# PowerManager.net
KiCad netlist of a schematic drawn in Altium Designer
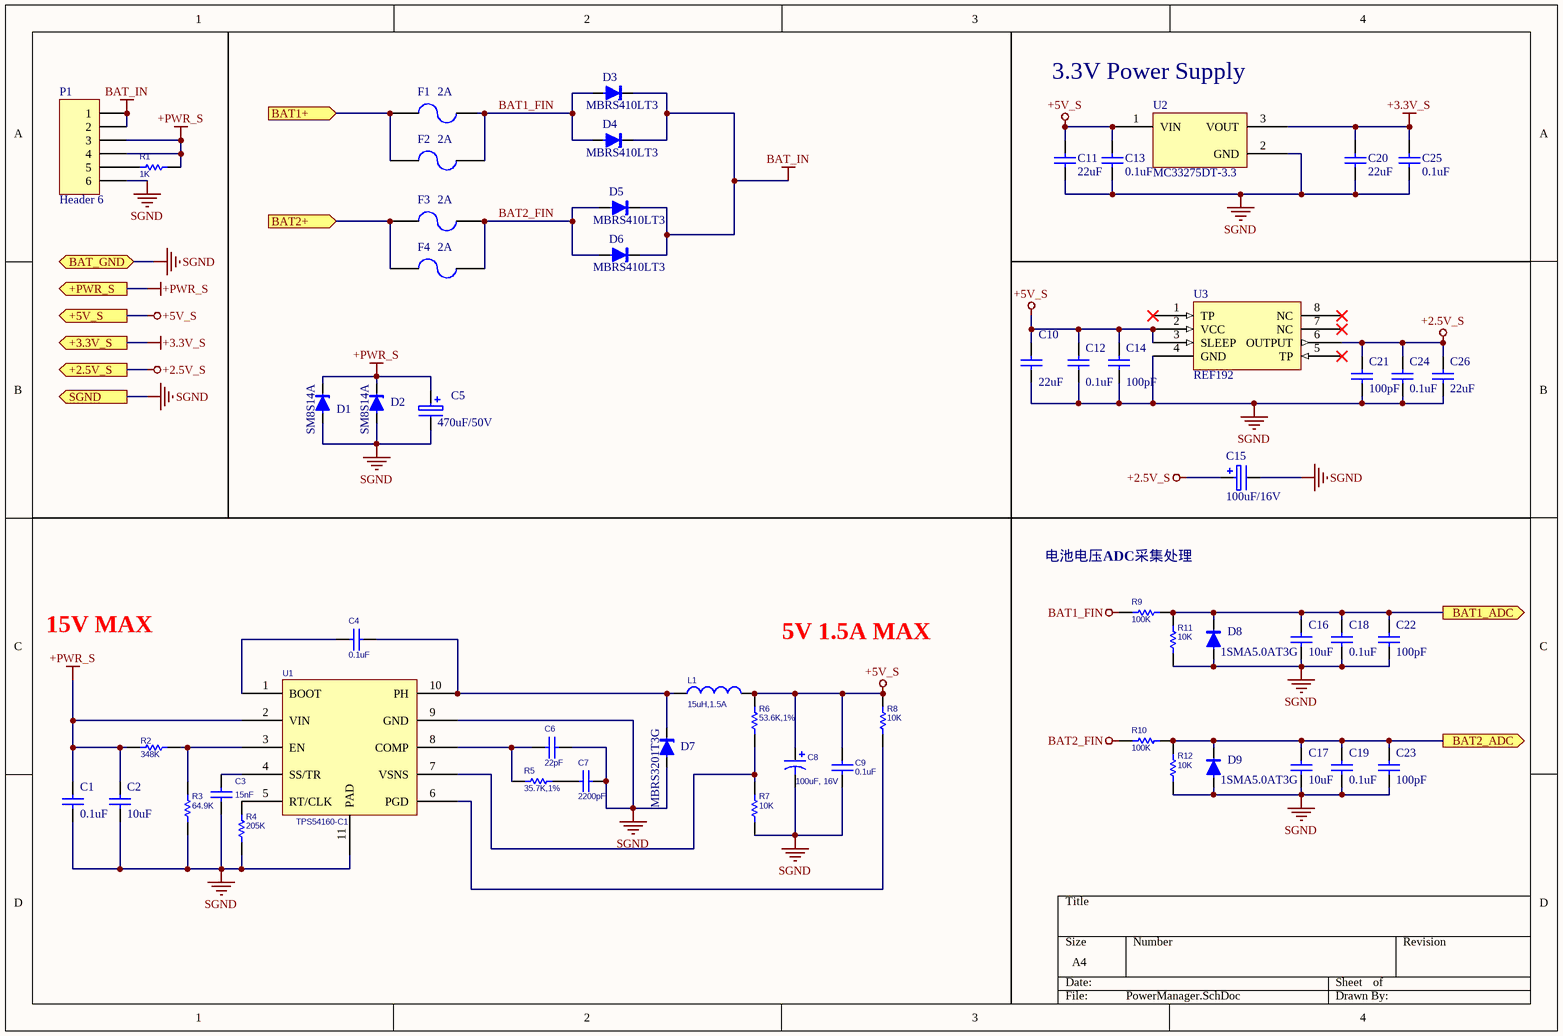
[diagram p0: PowerManager.SchDoc]

(export (version "E")
  (design (tool "Eeschema 10.0.6"))
  (components
    (comp (ref "C1")
      (value "0.1uF")
      (footprint "C0805")
      (description "CAP")
      (fields (field (name "PUBLISHER") "Altium Limited"))
      (libsource (lib "Passive Components Class") (part "CAP"))
    )
    (comp (ref "C2")
      (value "10uF")
      (footprint "C1206")
      (description "CAP")
      (fields (field (name "PUBLISHER") "Altium Limited"))
      (libsource (lib "Passive Components Class") (part "CAP"))
    )
    (comp (ref "C3")
      (value "15nF")
      (footprint "C0805")
      (description "CAP, CERAMIC, 15nF, 16V, X5R, 0603")
      (fields (field (name "PUBLISHER") "Altium Limited"))
      (libsource (lib "Miscellaneous Devices") (part "Cap"))
    )
    (comp (ref "C4")
      (value "0.1uF")
      (footprint "C0805")
      (description "CAP, CERAMIC, 0.1UF, 16V, X5R, 0603")
      (fields (field (name "PUBLISHER") "Altium Limited"))
      (libsource (lib "Miscellaneous Devices") (part "Cap"))
    )
    (comp (ref "C5")
      (value "470uF/50V")
      (footprint "CT7343-E")
      (description "Electrolytic Capacitor")
      (libsource (lib "*") (part "ELECTRO"))
    )
    (comp (ref "C6")
      (value "22pF")
      (footprint "R0805")
      (description "Capacitor")
      (fields (field (name "PUBLISHER") "Altium Limited"))
      (libsource (lib "Miscellaneous Devices") (part "Cap"))
    )
    (comp (ref "C7")
      (value "2200pF")
      (footprint "C0805")
      (description "Capacitor")
      (fields (field (name "PUBLISHER") "Altium Limited"))
      (libsource (lib "Miscellaneous Devices") (part "Cap"))
    )
    (comp (ref "C8")
      (value "100uF, 16V")
      (footprint "CT7343-E")
      (description "Polarized Capacitor (Radial)")
      (fields (field (name "PUBLISHER") "Altium Limited"))
      (libsource (lib "Miscellaneous Devices") (part "Cap Pol1"))
    )
    (comp (ref "C9")
      (value "0.1uF")
      (footprint "C0805")
      (description "CAP, CERAMIC, 0.1UF, 16V, X5R, 0603")
      (fields (field (name "PUBLISHER") "Altium Limited"))
      (libsource (lib "Miscellaneous Devices") (part "Cap"))
    )
    (comp (ref "C10")
      (value "22uF")
      (footprint "C1206")
      (description "CAP")
      (fields (field (name "PUBLISHER") "Altium Limited"))
      (libsource (lib "Passive Components Class") (part "CAP"))
    )
    (comp (ref "C11")
      (value "22uF")
      (footprint "C1206")
      (description "CAP")
      (fields (field (name "PUBLISHER") "Altium Limited"))
      (libsource (lib "Passive Components Class") (part "CAP"))
    )
    (comp (ref "C12")
      (value "0.1uF")
      (footprint "C0805")
      (description "CAP")
      (fields (field (name "PUBLISHER") "Altium Limited"))
      (libsource (lib "Passive Components Class") (part "CAP"))
    )
    (comp (ref "C13")
      (value "0.1uF")
      (footprint "C0805")
      (description "CAP")
      (fields (field (name "PUBLISHER") "Altium Limited"))
      (libsource (lib "Passive Components Class") (part "CAP"))
    )
    (comp (ref "C14")
      (value "100pF")
      (footprint "C0805")
      (description "CAP")
      (fields (field (name "PUBLISHER") "Altium Limited"))
      (libsource (lib "Passive Components Class") (part "CAP"))
    )
    (comp (ref "C15")
      (value "100uF/16V")
      (footprint "CT7343-E")
      (description "Electrolytic Capacitor")
      (libsource (lib "Passive Components Class") (part "CAP-ELECTRO"))
    )
    (comp (ref "C16")
      (value "10uF")
      (footprint "C1206")
      (description "CAP")
      (fields (field (name "PUBLISHER") "Altium Limited"))
      (libsource (lib "Passive Components Class") (part "CAP"))
    )
    (comp (ref "C17")
      (value "10uF")
      (footprint "C1206")
      (description "CAP")
      (fields (field (name "PUBLISHER") "Altium Limited"))
      (libsource (lib "Passive Components Class") (part "CAP"))
    )
    (comp (ref "C18")
      (value "0.1uF")
      (footprint "C1206")
      (description "CAP")
      (fields (field (name "PUBLISHER") "Altium Limited"))
      (libsource (lib "Passive Components Class") (part "CAP"))
    )
    (comp (ref "C19")
      (value "0.1uF")
      (footprint "C1206")
      (description "CAP")
      (fields (field (name "PUBLISHER") "Altium Limited"))
      (libsource (lib "Passive Components Class") (part "CAP"))
    )
    (comp (ref "C20")
      (value "22uF")
      (footprint "C1206")
      (description "CAP")
      (fields (field (name "PUBLISHER") "Altium Limited"))
      (libsource (lib "Passive Components Class") (part "CAP"))
    )
    (comp (ref "C21")
      (value "100pF")
      (footprint "C0805")
      (description "CAP")
      (fields (field (name "PUBLISHER") "Altium Limited"))
      (libsource (lib "Passive Components Class") (part "CAP"))
    )
    (comp (ref "C22")
      (value "100pF")
      (footprint "C1206")
      (description "CAP")
      (fields (field (name "PUBLISHER") "Altium Limited"))
      (libsource (lib "Passive Components Class") (part "CAP"))
    )
    (comp (ref "C23")
      (value "100pF")
      (footprint "C1206")
      (description "CAP")
      (fields (field (name "PUBLISHER") "Altium Limited"))
      (libsource (lib "Passive Components Class") (part "CAP"))
    )
    (comp (ref "C24")
      (value "0.1uF")
      (footprint "C0805")
      (description "CAP")
      (fields (field (name "PUBLISHER") "Altium Limited"))
      (libsource (lib "Passive Components Class") (part "CAP"))
    )
    (comp (ref "C25")
      (value "0.1uF")
      (footprint "C0805")
      (description "CAP")
      (fields (field (name "PUBLISHER") "Altium Limited"))
      (libsource (lib "Passive Components Class") (part "CAP"))
    )
    (comp (ref "C26")
      (value "22uF")
      (footprint "C1206")
      (description "CAP")
      (fields (field (name "PUBLISHER") "Altium Limited"))
      (libsource (lib "Passive Components Class") (part "CAP"))
    )
    (comp (ref "D1")
      (value "SM8S14A")
      (footprint "DO-218AB")
      (description "Small Signal Zener Diodes")
      (libsource (lib "Passive Components Class") (part "DIODE-ZENER"))
    )
    (comp (ref "D2")
      (value "SM8S14A")
      (footprint "DO-218AB")
      (description "Small Signal Zener Diodes")
      (libsource (lib "Passive Components Class") (part "DIODE-ZENER"))
    )
    (comp (ref "D3")
      (value "MBRS410LT3")
      (footprint "SMC")
      (description "Small Signal Zener Diodes")
      (libsource (lib "Passive Components Class") (part "DIODE-ZENER"))
    )
    (comp (ref "D4")
      (value "MBRS410LT3")
      (footprint "SMC")
      (description "Small Signal Zener Diodes")
      (libsource (lib "Passive Components Class") (part "DIODE-ZENER"))
    )
    (comp (ref "D5")
      (value "MBRS410LT3")
      (footprint "SMC")
      (description "Small Signal Zener Diodes")
      (libsource (lib "Passive Components Class") (part "DIODE-ZENER"))
    )
    (comp (ref "D6")
      (value "MBRS410LT3")
      (footprint "SMC")
      (description "Small Signal Zener Diodes")
      (libsource (lib "Passive Components Class") (part "DIODE-ZENER"))
    )
    (comp (ref "D7")
      (value "MBRS3201T3G")
      (footprint "DO-218AB")
      (description "Small Signal Zener Diodes")
      (libsource (lib "Passive Components Class") (part "DIODE-ZENER"))
    )
    (comp (ref "D8")
      (value "1SMA5.0AT3G")
      (footprint "SMA-S")
      (description "Silicon Epitaxial Planar Diodes")
      (libsource (lib "Passive Components Class") (part "DIODE-SWITCHING"))
    )
    (comp (ref "D9")
      (value "1SMA5.0AT3G")
      (footprint "SMA-S")
      (description "Silicon Epitaxial Planar Diodes")
      (libsource (lib "Passive Components Class") (part "DIODE-SWITCHING"))
    )
    (comp (ref "F1")
      (value "2A")
      (footprint "F1812")
      (description "Fuse")
      (libsource (lib "*") (part "FUSE2"))
    )
    (comp (ref "F2")
      (value "2A")
      (footprint "F1812")
      (description "Fuse")
      (libsource (lib "*") (part "FUSE2"))
    )
    (comp (ref "F3")
      (value "2A")
      (footprint "F1812")
      (description "Fuse")
      (libsource (lib "*") (part "FUSE2"))
    )
    (comp (ref "F4")
      (value "2A")
      (footprint "F1812")
      (description "Fuse")
      (libsource (lib "*") (part "FUSE2"))
    )
    (comp (ref "L1")
      (value "15uH,1.5A")
      (footprint "L5050-P")
      (description "Inductor")
      (fields (field (name "PUBLISHER") "Altium Limited"))
      (libsource (lib "Miscellaneous Devices") (part "Inductor"))
    )
    (comp (ref "P1")
      (value "Header 6")
      (footprint "DS1X6-2.54")
      (description "Header, 6-Pin")
      (fields (field (name "PUBLISHER") "Altium Limited"))
      (libsource (lib "Miscellaneous Connectors") (part "Header 6"))
    )
    (comp (ref "R1")
      (value "1K")
      (footprint "R0805")
      (description "Resistor")
      (fields (field (name "PUBLISHER") "Altium Limited"))
      (libsource (lib "Miscellaneous Devices") (part "Res1"))
    )
    (comp (ref "R2")
      (value "348K")
      (footprint "R0805")
      (description "Resistor")
      (fields (field (name "PUBLISHER") "Altium Limited"))
      (libsource (lib "Miscellaneous Devices") (part "Res1"))
    )
    (comp (ref "R3")
      (value "64.9K")
      (footprint "R0805")
      (description "Resistor")
      (fields (field (name "PUBLISHER") "Altium Limited"))
      (libsource (lib "Miscellaneous Devices") (part "Res1"))
    )
    (comp (ref "R4")
      (value "205K")
      (footprint "R0805")
      (description "Resistor")
      (fields (field (name "PUBLISHER") "Altium Limited"))
      (libsource (lib "Miscellaneous Devices") (part "Res1"))
    )
    (comp (ref "R5")
      (value "35.7K,1%")
      (footprint "R0805")
      (description "Resistor")
      (fields (field (name "PUBLISHER") "Altium Limited"))
      (libsource (lib "Miscellaneous Devices") (part "Res1"))
    )
    (comp (ref "R6")
      (value "53.6K,1%")
      (footprint "R0805")
      (description "Resistor")
      (fields (field (name "PUBLISHER") "Altium Limited"))
      (libsource (lib "Miscellaneous Devices") (part "Res1"))
    )
    (comp (ref "R7")
      (value "10K")
      (footprint "R0805")
      (description "Resistor")
      (fields (field (name "PUBLISHER") "Altium Limited"))
      (libsource (lib "Miscellaneous Devices") (part "Res1"))
    )
    (comp (ref "R8")
      (value "10K")
      (footprint "R0805")
      (description "Resistor")
      (fields (field (name "PUBLISHER") "Altium Limited"))
      (libsource (lib "Miscellaneous Devices") (part "Res1"))
    )
    (comp (ref "R9")
      (value "100K")
      (footprint "R0805")
      (description "Resistor")
      (fields (field (name "PUBLISHER") "Altium Limited"))
      (libsource (lib "Miscellaneous Devices") (part "Res1"))
    )
    (comp (ref "R10")
      (value "100K")
      (footprint "R0805")
      (description "Resistor")
      (fields (field (name "PUBLISHER") "Altium Limited"))
      (libsource (lib "Miscellaneous Devices") (part "Res1"))
    )
    (comp (ref "R11")
      (value "10K")
      (footprint "R0805")
      (description "Resistor")
      (fields (field (name "PUBLISHER") "Altium Limited"))
      (libsource (lib "Miscellaneous Devices") (part "Res1"))
    )
    (comp (ref "R12")
      (value "10K")
      (footprint "R0805")
      (description "Resistor")
      (fields (field (name "PUBLISHER") "Altium Limited"))
      (libsource (lib "Miscellaneous Devices") (part "Res1"))
    )
    (comp (ref "U1")
      (value "TPS54160-C1")
      (footprint "TSSO3X5-G10")
      (libsource (lib "AM3517_LIB") (part "TPS54160-C1"))
    )
    (comp (ref "U2")
      (value "MC33275DT-3.3")
      (footprint "TO-252")
      (description "3-Terminal 0.5A Positive Voltage Regulator")
      (fields (field (name "PUBLISHER") "Altium Limited"))
      (libsource (lib "Power Management Class") (part "MC78MXX"))
    )
    (comp (ref "U3") (value "REF192") (footprint "SO-8") (libsource (lib "tribute") (part "REF192/5/7")))
  )
  (nets
    (net (code "1") (name "+2.5V_S") (class "Default")
      (node (ref "C15") (pin "1") (pinfunction "1_1") (pintype "passive"))
      (node (ref "C21") (pin "2") (pinfunction "2_2") (pintype "passive"))
      (node (ref "C24") (pin "2") (pinfunction "2_2") (pintype "passive"))
      (node (ref "C26") (pin "2") (pinfunction "2_2") (pintype "passive"))
      (node (ref "U3") (pin "6") (pinfunction "OUTPUT_6") (pintype "output"))
    )
    (net (code "2") (name "+3.3V_S") (class "Default")
      (node (ref "C20") (pin "1") (pinfunction "1_1") (pintype "passive"))
      (node (ref "C25") (pin "2") (pinfunction "2_2") (pintype "passive"))
      (node (ref "U2") (pin "3") (pinfunction "VOUT_3") (pintype "passive"))
    )
    (net (code "3") (name "+5V_S") (class "Default")
      (node (ref "C10") (pin "2") (pinfunction "2_2") (pintype "passive"))
      (node (ref "C11") (pin "1") (pinfunction "1_1") (pintype "passive"))
      (node (ref "C12") (pin "2") (pinfunction "2_2") (pintype "passive"))
      (node (ref "C13") (pin "2") (pinfunction "2_2") (pintype "passive"))
      (node (ref "C14") (pin "2") (pinfunction "2_2") (pintype "passive"))
      (node (ref "C8") (pin "1") (pinfunction "1_1") (pintype "passive"))
      (node (ref "C9") (pin "1") (pinfunction "1_1") (pintype "passive"))
      (node (ref "L1") (pin "2") (pinfunction "2_2") (pintype "passive"))
      (node (ref "R6") (pin "2") (pinfunction "2_2") (pintype "passive"))
      (node (ref "R8") (pin "2") (pinfunction "2_2") (pintype "passive"))
      (node (ref "U2") (pin "1") (pinfunction "VIN_1") (pintype "passive"))
      (node (ref "U3") (pin "2") (pinfunction "VCC_2") (pintype "input"))
      (node (ref "U3") (pin "3") (pinfunction "SLEEP_3") (pintype "input"))
    )
    (net (code "4") (name "+PWR_S") (class "Default")
      (node (ref "C1") (pin "2") (pinfunction "2_2") (pintype "passive"))
      (node (ref "C2") (pin "2") (pinfunction "2_2") (pintype "passive"))
      (node (ref "C5") (pin "1") (pinfunction "1_1") (pintype "passive"))
      (node (ref "D1") (pin "2") (pinfunction "K_2") (pintype "passive"))
      (node (ref "D2") (pin "2") (pinfunction "K_2") (pintype "passive"))
      (node (ref "P1") (pin "3") (pinfunction "3_3") (pintype "passive"))
      (node (ref "P1") (pin "4") (pinfunction "4_4") (pintype "passive"))
      (node (ref "R1") (pin "1") (pinfunction "1_1") (pintype "passive"))
      (node (ref "R2") (pin "1") (pinfunction "1_1") (pintype "passive"))
      (node (ref "U1") (pin "2") (pinfunction "VIN_2") (pintype "passive"))
    )
    (net (code "5") (name "/BAT1+") (class "Default")
      (node (ref "F1") (pin "1") (pinfunction "1_1") (pintype "passive"))
      (node (ref "F2") (pin "1") (pinfunction "1_1") (pintype "passive"))
    )
    (net (code "6") (name "/BAT1_ADC") (class "Default")
      (node (ref "C16") (pin "2") (pinfunction "2_2") (pintype "passive"))
      (node (ref "C18") (pin "2") (pinfunction "2_2") (pintype "passive"))
      (node (ref "C22") (pin "2") (pinfunction "2_2") (pintype "passive"))
      (node (ref "D8") (pin "2") (pinfunction "K_2") (pintype "passive"))
      (node (ref "R11") (pin "1") (pinfunction "1_1") (pintype "passive"))
      (node (ref "R9") (pin "2") (pinfunction "2_2") (pintype "passive"))
    )
    (net (code "7") (name "/BAT2+") (class "Default")
      (node (ref "F3") (pin "1") (pinfunction "1_1") (pintype "passive"))
      (node (ref "F4") (pin "1") (pinfunction "1_1") (pintype "passive"))
    )
    (net (code "8") (name "/BAT2_ADC") (class "Default")
      (node (ref "C17") (pin "2") (pinfunction "2_2") (pintype "passive"))
      (node (ref "C19") (pin "2") (pinfunction "2_2") (pintype "passive"))
      (node (ref "C23") (pin "2") (pinfunction "2_2") (pintype "passive"))
      (node (ref "D9") (pin "2") (pinfunction "K_2") (pintype "passive"))
      (node (ref "R10") (pin "2") (pinfunction "2_2") (pintype "passive"))
      (node (ref "R12") (pin "1") (pinfunction "1_1") (pintype "passive"))
    )
    (net (code "9") (name "BAT1_FIN") (class "Default")
      (node (ref "D3") (pin "1") (pinfunction "A_1") (pintype "passive"))
      (node (ref "D4") (pin "1") (pinfunction "A_1") (pintype "passive"))
      (node (ref "F1") (pin "2") (pinfunction "2_2") (pintype "passive"))
      (node (ref "F2") (pin "2") (pinfunction "2_2") (pintype "passive"))
      (node (ref "R9") (pin "1") (pinfunction "1_1") (pintype "passive"))
    )
    (net (code "10") (name "BAT2_FIN") (class "Default")
      (node (ref "D5") (pin "1") (pinfunction "A_1") (pintype "passive"))
      (node (ref "D6") (pin "1") (pinfunction "A_1") (pintype "passive"))
      (node (ref "F3") (pin "2") (pinfunction "2_2") (pintype "passive"))
      (node (ref "F4") (pin "2") (pinfunction "2_2") (pintype "passive"))
      (node (ref "R10") (pin "1") (pinfunction "1_1") (pintype "passive"))
    )
    (net (code "11") (name "BAT_IN") (class "Default")
      (node (ref "D3") (pin "2") (pinfunction "K_2") (pintype "passive"))
      (node (ref "D4") (pin "2") (pinfunction "K_2") (pintype "passive"))
      (node (ref "D5") (pin "2") (pinfunction "K_2") (pintype "passive"))
      (node (ref "D6") (pin "2") (pinfunction "K_2") (pintype "passive"))
      (node (ref "P1") (pin "1") (pinfunction "1_1") (pintype "passive"))
      (node (ref "P1") (pin "2") (pinfunction "2_2") (pintype "passive"))
    )
    (net (code "12") (name "Net-(C7-Pad2)") (class "Default")
      (node (ref "C7") (pin "2") (pinfunction "2_2") (pintype "passive"))
      (node (ref "R5") (pin "1") (pinfunction "1_1") (pintype "passive"))
    )
    (net (code "13") (name "Net-(D7-K)") (class "Default")
      (node (ref "C4") (pin "1") (pinfunction "1_1") (pintype "passive"))
      (node (ref "D7") (pin "2") (pinfunction "K_2") (pintype "passive"))
      (node (ref "L1") (pin "1") (pinfunction "1_1") (pintype "passive"))
      (node (ref "U1") (pin "10") (pinfunction "PH_10") (pintype "passive"))
    )
    (net (code "14") (name "Net-(P1-Pad5)") (class "Default")
      (node (ref "P1") (pin "5") (pinfunction "5_5") (pintype "passive"))
      (node (ref "R1") (pin "2") (pinfunction "2_2") (pintype "passive"))
    )
    (net (code "15") (name "Net-(U1-BOOT)") (class "Default")
      (node (ref "C4") (pin "2") (pinfunction "2_2") (pintype "passive"))
      (node (ref "U1") (pin "1") (pinfunction "BOOT_1") (pintype "passive"))
    )
    (net (code "16") (name "Net-(U1-COMP)") (class "Default")
      (node (ref "C6") (pin "2") (pinfunction "2_2") (pintype "passive"))
      (node (ref "R5") (pin "2") (pinfunction "2_2") (pintype "passive"))
      (node (ref "U1") (pin "8") (pinfunction "COMP_8") (pintype "passive"))
    )
    (net (code "17") (name "Net-(U1-EN)") (class "Default")
      (node (ref "R2") (pin "2") (pinfunction "2_2") (pintype "passive"))
      (node (ref "R3") (pin "2") (pinfunction "2_2") (pintype "passive"))
      (node (ref "U1") (pin "3") (pinfunction "EN_3") (pintype "passive"))
    )
    (net (code "18") (name "Net-(U1-PGD)") (class "Default")
      (node (ref "R8") (pin "1") (pinfunction "1_1") (pintype "passive"))
      (node (ref "U1") (pin "6") (pinfunction "PGD_6") (pintype "passive"))
    )
    (net (code "19") (name "Net-(U1-RT{slash}CLK)") (class "Default")
      (node (ref "R4") (pin "2") (pinfunction "2_2") (pintype "passive"))
      (node (ref "U1") (pin "5") (pinfunction "RT/CLK_5") (pintype "passive"))
    )
    (net (code "20") (name "Net-(U1-SS{slash}TR)") (class "Default")
      (node (ref "C3") (pin "2") (pinfunction "2_2") (pintype "passive"))
      (node (ref "U1") (pin "4") (pinfunction "SS/TR_4") (pintype "passive"))
    )
    (net (code "21") (name "Net-(U1-VSNS)") (class "Default")
      (node (ref "R6") (pin "1") (pinfunction "1_1") (pintype "passive"))
      (node (ref "R7") (pin "2") (pinfunction "2_2") (pintype "passive"))
      (node (ref "U1") (pin "7") (pinfunction "VSNS_7") (pintype "passive"))
    )
    (net (code "22") (name "SGND") (class "Default")
      (node (ref "C1") (pin "1") (pinfunction "1_1") (pintype "passive"))
      (node (ref "C10") (pin "1") (pinfunction "1_1") (pintype "passive"))
      (node (ref "C11") (pin "2") (pinfunction "2_2") (pintype "passive"))
      (node (ref "C12") (pin "1") (pinfunction "1_1") (pintype "passive"))
      (node (ref "C13") (pin "1") (pinfunction "1_1") (pintype "passive"))
      (node (ref "C14") (pin "1") (pinfunction "1_1") (pintype "passive"))
      (node (ref "C15") (pin "2") (pinfunction "2_2") (pintype "passive"))
      (node (ref "C16") (pin "1") (pinfunction "1_1") (pintype "passive"))
      (node (ref "C17") (pin "1") (pinfunction "1_1") (pintype "passive"))
      (node (ref "C18") (pin "1") (pinfunction "1_1") (pintype "passive"))
      (node (ref "C19") (pin "1") (pinfunction "1_1") (pintype "passive"))
      (node (ref "C2") (pin "1") (pinfunction "1_1") (pintype "passive"))
      (node (ref "C20") (pin "2") (pinfunction "2_2") (pintype "passive"))
      (node (ref "C21") (pin "1") (pinfunction "1_1") (pintype "passive"))
      (node (ref "C22") (pin "1") (pinfunction "1_1") (pintype "passive"))
      (node (ref "C23") (pin "1") (pinfunction "1_1") (pintype "passive"))
      (node (ref "C24") (pin "1") (pinfunction "1_1") (pintype "passive"))
      (node (ref "C25") (pin "1") (pinfunction "1_1") (pintype "passive"))
      (node (ref "C26") (pin "1") (pinfunction "1_1") (pintype "passive"))
      (node (ref "C3") (pin "1") (pinfunction "1_1") (pintype "passive"))
      (node (ref "C5") (pin "2") (pinfunction "2_2") (pintype "passive"))
      (node (ref "C6") (pin "1") (pinfunction "1_1") (pintype "passive"))
      (node (ref "C7") (pin "1") (pinfunction "1_1") (pintype "passive"))
      (node (ref "C8") (pin "2") (pinfunction "2_2") (pintype "passive"))
      (node (ref "C9") (pin "2") (pinfunction "2_2") (pintype "passive"))
      (node (ref "D1") (pin "1") (pinfunction "A_1") (pintype "passive"))
      (node (ref "D2") (pin "1") (pinfunction "A_1") (pintype "passive"))
      (node (ref "D7") (pin "1") (pinfunction "A_1") (pintype "passive"))
      (node (ref "D8") (pin "1") (pinfunction "A_1") (pintype "passive"))
      (node (ref "D9") (pin "1") (pinfunction "A_1") (pintype "passive"))
      (node (ref "P1") (pin "6") (pinfunction "6_6") (pintype "passive"))
      (node (ref "R11") (pin "2") (pinfunction "2_2") (pintype "passive"))
      (node (ref "R12") (pin "2") (pinfunction "2_2") (pintype "passive"))
      (node (ref "R3") (pin "1") (pinfunction "1_1") (pintype "passive"))
      (node (ref "R4") (pin "1") (pinfunction "1_1") (pintype "passive"))
      (node (ref "R7") (pin "1") (pinfunction "1_1") (pintype "passive"))
      (node (ref "U1") (pin "11") (pinfunction "PAD_11") (pintype "passive"))
      (node (ref "U1") (pin "9") (pinfunction "GND_9") (pintype "passive"))
      (node (ref "U2") (pin "2") (pinfunction "GND_2") (pintype "passive"))
      (node (ref "U3") (pin "4") (pinfunction "GND_4") (pintype "power_in"))
    )
    (net (code "23") (name "unconnected-(U3-NC-Pad7)") (class "Default")
      (node (ref "U3") (pin "7") (pinfunction "NC_7") (pintype "passive+no_connect"))
    )
    (net (code "24") (name "unconnected-(U3-NC-Pad8)") (class "Default")
      (node (ref "U3") (pin "8") (pinfunction "NC_8") (pintype "passive+no_connect"))
    )
    (net (code "25") (name "unconnected-(U3-TP-Pad1)") (class "Default")
      (node (ref "U3") (pin "1") (pinfunction "TP_1") (pintype "input+no_connect"))
    )
    (net (code "26") (name "unconnected-(U3-TP-Pad5)") (class "Default")
      (node (ref "U3") (pin "5") (pinfunction "TP_5") (pintype "input+no_connect"))
    )
  )
)
